# TK525_Hovedstrom.net
KiCad netlist of a schematic drawn in Altium Designer
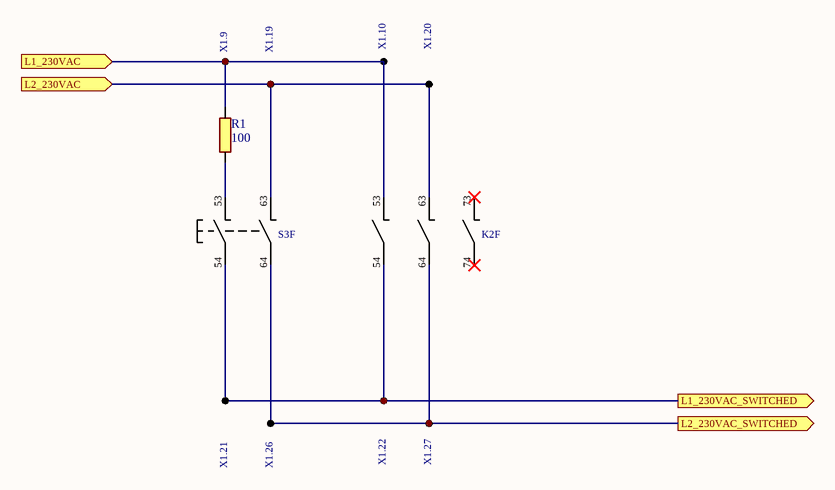
[diagram p0: TK525_Hovedstrom.SchDoc]

(export (version "E")
  (design (tool "Eeschema 10.0.6"))
  (components
    (comp (ref "K2")
      (value "Kontaktor")
      (description "Industriellt rele")
      (libsource (lib "OVLib") (part "Contactor"))
    )
    (comp (ref "R1")
      (value "100")
      (footprint "RESA_0.25W")
      (description "0.25W 1% Generic resistor")
      (libsource (lib "OVLib") (part "Resistor2"))
    )
    (comp (ref "S3")
      (value "Automasjonsbryter")
      (description "Kraftig")
      (libsource (lib "OVLib") (part "AutomationSwitch"))
    )
    (comp (ref "X1.9")
      (value "Rekkeklemme 2.5mm2")
      (description "DIN Rail mount terminal block")
      (libsource (lib "OVLib") (part "Punkt"))
    )
    (comp (ref "X1.10")
      (value "Rekkeklemme 2.5mm2")
      (description "DIN Rail mount terminal block")
      (libsource (lib "OVLib") (part "Punkt"))
    )
    (comp (ref "X1.19")
      (value "Rekkeklemme 2.5mm2")
      (description "DIN Rail mount terminal block")
      (libsource (lib "OVLib") (part "Punkt"))
    )
    (comp (ref "X1.20")
      (value "Rekkeklemme 2.5mm2")
      (description "DIN Rail mount terminal block")
      (libsource (lib "OVLib") (part "Punkt"))
    )
    (comp (ref "X1.21")
      (value "Rekkeklemme 2.5mm2")
      (description "DIN Rail mount terminal block")
      (libsource (lib "OVLib") (part "Punkt"))
    )
    (comp (ref "X1.22")
      (value "Rekkeklemme 2.5mm2")
      (description "DIN Rail mount terminal block")
      (libsource (lib "OVLib") (part "Punkt"))
    )
    (comp (ref "X1.26")
      (value "Rekkeklemme 2.5mm2")
      (description "DIN Rail mount terminal block")
      (libsource (lib "OVLib") (part "Punkt"))
    )
    (comp (ref "X1.27")
      (value "Rekkeklemme 2.5mm2")
      (description "DIN Rail mount terminal block")
      (libsource (lib "OVLib") (part "Punkt"))
    )
  )
  (nets
    (net (code "1") (name "/L1_230VAC") (class "Default")
      (node (ref "K2") (pin "53") (pinfunction "53_53") (pintype "passive"))
      (node (ref "R1") (pin "2") (pinfunction "2_2") (pintype "passive"))
    )
    (net (code "2") (name "/L1_230VAC_SWITCHED") (class "Default")
      (node (ref "K2") (pin "54") (pinfunction "54_54") (pintype "passive"))
      (node (ref "S3") (pin "54") (pinfunction "54_54") (pintype "passive"))
    )
    (net (code "3") (name "/L2_230VAC") (class "Default")
      (node (ref "K2") (pin "63") (pinfunction "63_63") (pintype "passive"))
      (node (ref "S3") (pin "63") (pinfunction "63_63") (pintype "passive"))
    )
    (net (code "4") (name "/L2_230VAC_SWITCHED") (class "Default")
      (node (ref "K2") (pin "64") (pinfunction "64_64") (pintype "passive"))
      (node (ref "S3") (pin "64") (pinfunction "64_64") (pintype "passive"))
    )
    (net (code "5") (name "Net-(R1-Pad1)") (class "Default")
      (node (ref "R1") (pin "1") (pinfunction "1_1") (pintype "passive"))
      (node (ref "S3") (pin "53") (pinfunction "53_53") (pintype "passive"))
    )
    (net (code "6") (name "unconnected-(K2-Pad73)") (class "Default")
      (node (ref "K2") (pin "73") (pinfunction "73_73") (pintype "passive+no_connect"))
    )
    (net (code "7") (name "unconnected-(K2-Pad74)") (class "Default")
      (node (ref "K2") (pin "74") (pinfunction "74_74") (pintype "passive+no_connect"))
    )
  )
)
